# calculator2.net
KiCad netlist of a schematic drawn in EAGLE
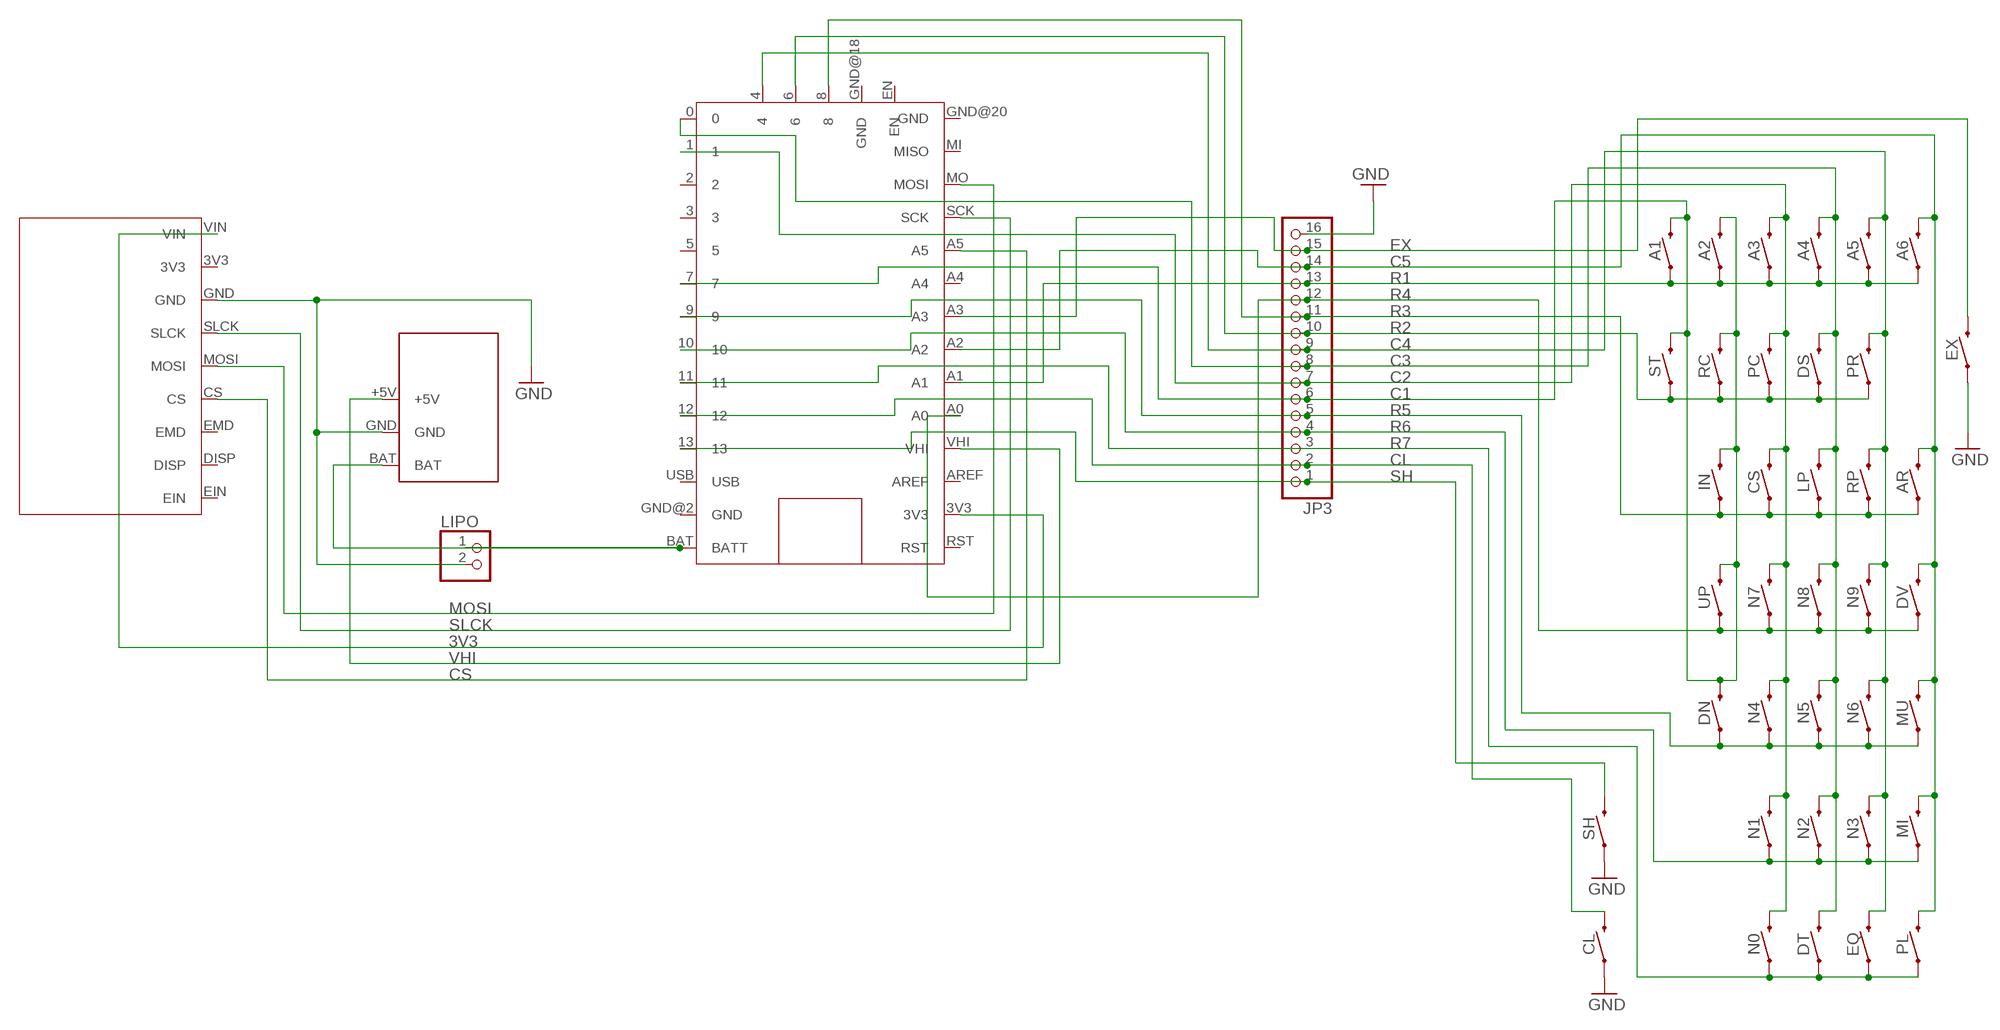
[diagram p0: schematic, sheet 1]

(export (version "E")
  (design (tool "Eeschema 10.0.6"))
  (components
    (comp (ref "A1")
      (value "MOMENTARY-SWITCH-SPST-PTH-6.0MM")
      (footprint "eagle-import:TACTILE_SWITCH_PTH_6.0MM")
      (libsource (lib "eagle-import") (part "MOMENTARY-SWITCH-SPST-PTH-6.0MM"))
    )
    (comp (ref "A2")
      (value "MOMENTARY-SWITCH-SPST-PTH-6.0MM")
      (footprint "eagle-import:TACTILE_SWITCH_PTH_6.0MM")
      (libsource (lib "eagle-import") (part "MOMENTARY-SWITCH-SPST-PTH-6.0MM"))
    )
    (comp (ref "A3")
      (value "MOMENTARY-SWITCH-SPST-PTH-6.0MM")
      (footprint "eagle-import:TACTILE_SWITCH_PTH_6.0MM")
      (libsource (lib "eagle-import") (part "MOMENTARY-SWITCH-SPST-PTH-6.0MM"))
    )
    (comp (ref "A4")
      (value "MOMENTARY-SWITCH-SPST-PTH-6.0MM")
      (footprint "eagle-import:TACTILE_SWITCH_PTH_6.0MM")
      (libsource (lib "eagle-import") (part "MOMENTARY-SWITCH-SPST-PTH-6.0MM"))
    )
    (comp (ref "A5")
      (value "MOMENTARY-SWITCH-SPST-PTH-6.0MM")
      (footprint "eagle-import:TACTILE_SWITCH_PTH_6.0MM")
      (libsource (lib "eagle-import") (part "MOMENTARY-SWITCH-SPST-PTH-6.0MM"))
    )
    (comp (ref "A6")
      (value "MOMENTARY-SWITCH-SPST-PTH-6.0MM")
      (footprint "eagle-import:TACTILE_SWITCH_PTH_6.0MM")
      (libsource (lib "eagle-import") (part "MOMENTARY-SWITCH-SPST-PTH-6.0MM"))
    )
    (comp (ref "AR")
      (value "MOMENTARY-SWITCH-SPST-PTH-6.0MM")
      (footprint "eagle-import:TACTILE_SWITCH_PTH_6.0MM")
      (libsource (lib "eagle-import") (part "MOMENTARY-SWITCH-SPST-PTH-6.0MM"))
    )
    (comp (ref "CHARGER")
      (value "PROTRINKET")
      (footprint "eagle-import:PROTRINKET")
      (libsource (lib "eagle-import") (part "PROTRINKET"))
    )
    (comp (ref "CL")
      (value "MOMENTARY-SWITCH-SPST-PTH-6.0MM")
      (footprint "eagle-import:TACTILE_SWITCH_PTH_6.0MM")
      (libsource (lib "eagle-import") (part "MOMENTARY-SWITCH-SPST-PTH-6.0MM"))
    )
    (comp (ref "CONTROLLER")
      (value "IB32U4")
      (footprint "eagle-import:IB32U4")
      (libsource (lib "eagle-import") (part "IB32U4"))
    )
    (comp (ref "CS")
      (value "MOMENTARY-SWITCH-SPST-PTH-6.0MM")
      (footprint "eagle-import:TACTILE_SWITCH_PTH_6.0MM")
      (libsource (lib "eagle-import") (part "MOMENTARY-SWITCH-SPST-PTH-6.0MM"))
    )
    (comp (ref "DN")
      (value "MOMENTARY-SWITCH-SPST-PTH-6.0MM")
      (footprint "eagle-import:TACTILE_SWITCH_PTH_6.0MM")
      (libsource (lib "eagle-import") (part "MOMENTARY-SWITCH-SPST-PTH-6.0MM"))
    )
    (comp (ref "DS")
      (value "MOMENTARY-SWITCH-SPST-PTH-6.0MM")
      (footprint "eagle-import:TACTILE_SWITCH_PTH_6.0MM")
      (libsource (lib "eagle-import") (part "MOMENTARY-SWITCH-SPST-PTH-6.0MM"))
    )
    (comp (ref "DT")
      (value "MOMENTARY-SWITCH-SPST-PTH-6.0MM")
      (footprint "eagle-import:TACTILE_SWITCH_PTH_6.0MM")
      (libsource (lib "eagle-import") (part "MOMENTARY-SWITCH-SPST-PTH-6.0MM"))
    )
    (comp (ref "DV")
      (value "MOMENTARY-SWITCH-SPST-PTH-6.0MM")
      (footprint "eagle-import:TACTILE_SWITCH_PTH_6.0MM")
      (libsource (lib "eagle-import") (part "MOMENTARY-SWITCH-SPST-PTH-6.0MM"))
    )
    (comp (ref "EQ")
      (value "MOMENTARY-SWITCH-SPST-PTH-6.0MM")
      (footprint "eagle-import:TACTILE_SWITCH_PTH_6.0MM")
      (libsource (lib "eagle-import") (part "MOMENTARY-SWITCH-SPST-PTH-6.0MM"))
    )
    (comp (ref "EX")
      (value "MOMENTARY-SWITCH-SPST-PTH-6.0MM")
      (footprint "eagle-import:TACTILE_SWITCH_PTH_6.0MM")
      (libsource (lib "eagle-import") (part "MOMENTARY-SWITCH-SPST-PTH-6.0MM"))
    )
    (comp (ref "IN")
      (value "MOMENTARY-SWITCH-SPST-PTH-6.0MM")
      (footprint "eagle-import:TACTILE_SWITCH_PTH_6.0MM")
      (libsource (lib "eagle-import") (part "MOMENTARY-SWITCH-SPST-PTH-6.0MM"))
    )
    (comp (ref "JP3")
      (value "PINHD-1X16")
      (footprint "eagle-import:1X16")
      (libsource (lib "eagle-import") (part "PINHD-1X16"))
    )
    (comp (ref "LIPO")
      (value "PINHD-1X2")
      (footprint "eagle-import:1X02")
      (libsource (lib "eagle-import") (part "PINHD-1X2"))
    )
    (comp (ref "LP")
      (value "MOMENTARY-SWITCH-SPST-PTH-6.0MM")
      (footprint "eagle-import:TACTILE_SWITCH_PTH_6.0MM")
      (libsource (lib "eagle-import") (part "MOMENTARY-SWITCH-SPST-PTH-6.0MM"))
    )
    (comp (ref "MI")
      (value "MOMENTARY-SWITCH-SPST-PTH-6.0MM")
      (footprint "eagle-import:TACTILE_SWITCH_PTH_6.0MM")
      (libsource (lib "eagle-import") (part "MOMENTARY-SWITCH-SPST-PTH-6.0MM"))
    )
    (comp (ref "MU")
      (value "MOMENTARY-SWITCH-SPST-PTH-6.0MM")
      (footprint "eagle-import:TACTILE_SWITCH_PTH_6.0MM")
      (libsource (lib "eagle-import") (part "MOMENTARY-SWITCH-SPST-PTH-6.0MM"))
    )
    (comp (ref "N0")
      (value "MOMENTARY-SWITCH-SPST-PTH-6.0MM")
      (footprint "eagle-import:TACTILE_SWITCH_PTH_6.0MM")
      (libsource (lib "eagle-import") (part "MOMENTARY-SWITCH-SPST-PTH-6.0MM"))
    )
    (comp (ref "N1")
      (value "MOMENTARY-SWITCH-SPST-PTH-6.0MM")
      (footprint "eagle-import:TACTILE_SWITCH_PTH_6.0MM")
      (libsource (lib "eagle-import") (part "MOMENTARY-SWITCH-SPST-PTH-6.0MM"))
    )
    (comp (ref "N2")
      (value "MOMENTARY-SWITCH-SPST-PTH-6.0MM")
      (footprint "eagle-import:TACTILE_SWITCH_PTH_6.0MM")
      (libsource (lib "eagle-import") (part "MOMENTARY-SWITCH-SPST-PTH-6.0MM"))
    )
    (comp (ref "N3")
      (value "MOMENTARY-SWITCH-SPST-PTH-6.0MM")
      (footprint "eagle-import:TACTILE_SWITCH_PTH_6.0MM")
      (libsource (lib "eagle-import") (part "MOMENTARY-SWITCH-SPST-PTH-6.0MM"))
    )
    (comp (ref "N4")
      (value "MOMENTARY-SWITCH-SPST-PTH-6.0MM")
      (footprint "eagle-import:TACTILE_SWITCH_PTH_6.0MM")
      (libsource (lib "eagle-import") (part "MOMENTARY-SWITCH-SPST-PTH-6.0MM"))
    )
    (comp (ref "N5")
      (value "MOMENTARY-SWITCH-SPST-PTH-6.0MM")
      (footprint "eagle-import:TACTILE_SWITCH_PTH_6.0MM")
      (libsource (lib "eagle-import") (part "MOMENTARY-SWITCH-SPST-PTH-6.0MM"))
    )
    (comp (ref "N6")
      (value "MOMENTARY-SWITCH-SPST-PTH-6.0MM")
      (footprint "eagle-import:TACTILE_SWITCH_PTH_6.0MM")
      (libsource (lib "eagle-import") (part "MOMENTARY-SWITCH-SPST-PTH-6.0MM"))
    )
    (comp (ref "N7")
      (value "MOMENTARY-SWITCH-SPST-PTH-6.0MM")
      (footprint "eagle-import:TACTILE_SWITCH_PTH_6.0MM")
      (libsource (lib "eagle-import") (part "MOMENTARY-SWITCH-SPST-PTH-6.0MM"))
    )
    (comp (ref "N8")
      (value "MOMENTARY-SWITCH-SPST-PTH-6.0MM")
      (footprint "eagle-import:TACTILE_SWITCH_PTH_6.0MM")
      (libsource (lib "eagle-import") (part "MOMENTARY-SWITCH-SPST-PTH-6.0MM"))
    )
    (comp (ref "N9")
      (value "MOMENTARY-SWITCH-SPST-PTH-6.0MM")
      (footprint "eagle-import:TACTILE_SWITCH_PTH_6.0MM")
      (libsource (lib "eagle-import") (part "MOMENTARY-SWITCH-SPST-PTH-6.0MM"))
    )
    (comp (ref "PC")
      (value "MOMENTARY-SWITCH-SPST-PTH-6.0MM")
      (footprint "eagle-import:TACTILE_SWITCH_PTH_6.0MM")
      (libsource (lib "eagle-import") (part "MOMENTARY-SWITCH-SPST-PTH-6.0MM"))
    )
    (comp (ref "PL")
      (value "MOMENTARY-SWITCH-SPST-PTH-6.0MM")
      (footprint "eagle-import:TACTILE_SWITCH_PTH_6.0MM")
      (libsource (lib "eagle-import") (part "MOMENTARY-SWITCH-SPST-PTH-6.0MM"))
    )
    (comp (ref "PR")
      (value "MOMENTARY-SWITCH-SPST-PTH-6.0MM")
      (footprint "eagle-import:TACTILE_SWITCH_PTH_6.0MM")
      (libsource (lib "eagle-import") (part "MOMENTARY-SWITCH-SPST-PTH-6.0MM"))
    )
    (comp (ref "RC")
      (value "MOMENTARY-SWITCH-SPST-PTH-6.0MM")
      (footprint "eagle-import:TACTILE_SWITCH_PTH_6.0MM")
      (libsource (lib "eagle-import") (part "MOMENTARY-SWITCH-SPST-PTH-6.0MM"))
    )
    (comp (ref "RP")
      (value "MOMENTARY-SWITCH-SPST-PTH-6.0MM")
      (footprint "eagle-import:TACTILE_SWITCH_PTH_6.0MM")
      (libsource (lib "eagle-import") (part "MOMENTARY-SWITCH-SPST-PTH-6.0MM"))
    )
    (comp (ref "SH")
      (value "MOMENTARY-SWITCH-SPST-PTH-6.0MM")
      (footprint "eagle-import:TACTILE_SWITCH_PTH_6.0MM")
      (libsource (lib "eagle-import") (part "MOMENTARY-SWITCH-SPST-PTH-6.0MM"))
    )
    (comp (ref "SHARPMEM")
      (value "SHARPMEM")
      (footprint "eagle-import:SHARPMEM")
      (libsource (lib "eagle-import") (part "SHARPMEM"))
    )
    (comp (ref "ST")
      (value "MOMENTARY-SWITCH-SPST-PTH-6.0MM")
      (footprint "eagle-import:TACTILE_SWITCH_PTH_6.0MM")
      (libsource (lib "eagle-import") (part "MOMENTARY-SWITCH-SPST-PTH-6.0MM"))
    )
    (comp (ref "UP")
      (value "MOMENTARY-SWITCH-SPST-PTH-6.0MM")
      (footprint "eagle-import:TACTILE_SWITCH_PTH_6.0MM")
      (libsource (lib "eagle-import") (part "MOMENTARY-SWITCH-SPST-PTH-6.0MM"))
    )
  )
  (nets
    (net (code "1") (name "/3V3") (class "Default")
      (node (ref "CONTROLLER") (pin "3V3") (pinfunction "3V3_3V3") (pintype "bidirectional"))
      (node (ref "SHARPMEM") (pin "VIN") (pinfunction "VIN_VIN") (pintype "bidirectional"))
    )
    (net (code "2") (name "/C1") (class "Default")
      (node (ref "A1") (pin "3") (pinfunction "2_3") (pintype "passive"))
      (node (ref "A2") (pin "3") (pinfunction "2_3") (pintype "passive"))
      (node (ref "CONTROLLER") (pin "7") (pinfunction "7_7") (pintype "bidirectional"))
      (node (ref "DN") (pin "3") (pinfunction "2_3") (pintype "passive"))
      (node (ref "IN") (pin "3") (pinfunction "2_3") (pintype "passive"))
      (node (ref "JP3") (pin "6") (pinfunction "6_6") (pintype "passive"))
      (node (ref "RC") (pin "3") (pinfunction "2_3") (pintype "passive"))
      (node (ref "ST") (pin "3") (pinfunction "2_3") (pintype "passive"))
      (node (ref "UP") (pin "3") (pinfunction "2_3") (pintype "passive"))
    )
    (net (code "3") (name "/C2") (class "Default")
      (node (ref "A3") (pin "3") (pinfunction "2_3") (pintype "passive"))
      (node (ref "CONTROLLER") (pin "1") (pinfunction "1_1") (pintype "bidirectional"))
      (node (ref "CS") (pin "3") (pinfunction "2_3") (pintype "passive"))
      (node (ref "JP3") (pin "7") (pinfunction "7_7") (pintype "passive"))
      (node (ref "N0") (pin "3") (pinfunction "2_3") (pintype "passive"))
      (node (ref "N1") (pin "3") (pinfunction "2_3") (pintype "passive"))
      (node (ref "N4") (pin "3") (pinfunction "2_3") (pintype "passive"))
      (node (ref "N7") (pin "3") (pinfunction "2_3") (pintype "passive"))
      (node (ref "PC") (pin "3") (pinfunction "2_3") (pintype "passive"))
    )
    (net (code "4") (name "/C3") (class "Default")
      (node (ref "A4") (pin "3") (pinfunction "2_3") (pintype "passive"))
      (node (ref "CONTROLLER") (pin "0") (pinfunction "0_0") (pintype "bidirectional"))
      (node (ref "DS") (pin "3") (pinfunction "2_3") (pintype "passive"))
      (node (ref "DT") (pin "3") (pinfunction "2_3") (pintype "passive"))
      (node (ref "JP3") (pin "8") (pinfunction "8_8") (pintype "passive"))
      (node (ref "LP") (pin "3") (pinfunction "2_3") (pintype "passive"))
      (node (ref "N2") (pin "3") (pinfunction "2_3") (pintype "passive"))
      (node (ref "N5") (pin "3") (pinfunction "2_3") (pintype "passive"))
      (node (ref "N8") (pin "3") (pinfunction "2_3") (pintype "passive"))
    )
    (net (code "5") (name "/C4") (class "Default")
      (node (ref "A5") (pin "3") (pinfunction "2_3") (pintype "passive"))
      (node (ref "CONTROLLER") (pin "4") (pinfunction "4_4") (pintype "bidirectional"))
      (node (ref "EQ") (pin "3") (pinfunction "2_3") (pintype "passive"))
      (node (ref "JP3") (pin "9") (pinfunction "9_9") (pintype "passive"))
      (node (ref "N3") (pin "3") (pinfunction "2_3") (pintype "passive"))
      (node (ref "N6") (pin "3") (pinfunction "2_3") (pintype "passive"))
      (node (ref "N9") (pin "3") (pinfunction "2_3") (pintype "passive"))
      (node (ref "PR") (pin "3") (pinfunction "2_3") (pintype "passive"))
      (node (ref "RP") (pin "3") (pinfunction "2_3") (pintype "passive"))
    )
    (net (code "6") (name "/C5") (class "Default")
      (node (ref "A6") (pin "3") (pinfunction "2_3") (pintype "passive"))
      (node (ref "AR") (pin "3") (pinfunction "2_3") (pintype "passive"))
      (node (ref "CONTROLLER") (pin "A2") (pinfunction "A2_A2") (pintype "bidirectional"))
      (node (ref "DV") (pin "3") (pinfunction "2_3") (pintype "passive"))
      (node (ref "JP3") (pin "14") (pinfunction "14_14") (pintype "passive"))
      (node (ref "MI") (pin "3") (pinfunction "2_3") (pintype "passive"))
      (node (ref "MU") (pin "3") (pinfunction "2_3") (pintype "passive"))
      (node (ref "PL") (pin "3") (pinfunction "2_3") (pintype "passive"))
    )
    (net (code "7") (name "/CL") (class "Default")
      (node (ref "CL") (pin "3") (pinfunction "2_3") (pintype "passive"))
      (node (ref "CONTROLLER") (pin "12") (pinfunction "12_12") (pintype "bidirectional"))
      (node (ref "JP3") (pin "2") (pinfunction "2_2") (pintype "passive"))
    )
    (net (code "8") (name "/CS") (class "Default")
      (node (ref "CONTROLLER") (pin "A5") (pinfunction "A5_A5") (pintype "bidirectional"))
      (node (ref "SHARPMEM") (pin "CS") (pinfunction "CS_CS") (pintype "bidirectional"))
    )
    (net (code "9") (name "/EX") (class "Default")
      (node (ref "CONTROLLER") (pin "A3") (pinfunction "A3_A3") (pintype "bidirectional"))
      (node (ref "EX") (pin "3") (pinfunction "2_3") (pintype "passive"))
      (node (ref "JP3") (pin "15") (pinfunction "15_15") (pintype "passive"))
    )
    (net (code "10") (name "/MOSI") (class "Default")
      (node (ref "CONTROLLER") (pin "MO") (pinfunction "MOSI_MO") (pintype "bidirectional"))
      (node (ref "SHARPMEM") (pin "MOSI") (pinfunction "MOSI_MOSI") (pintype "bidirectional"))
    )
    (net (code "11") (name "/R1") (class "Default")
      (node (ref "A1") (pin "1") (pinfunction "1_1") (pintype "passive"))
      (node (ref "A2") (pin "1") (pinfunction "1_1") (pintype "passive"))
      (node (ref "A3") (pin "1") (pinfunction "1_1") (pintype "passive"))
      (node (ref "A4") (pin "1") (pinfunction "1_1") (pintype "passive"))
      (node (ref "A5") (pin "1") (pinfunction "1_1") (pintype "passive"))
      (node (ref "A6") (pin "1") (pinfunction "1_1") (pintype "passive"))
      (node (ref "CONTROLLER") (pin "A1") (pinfunction "A1_A1") (pintype "bidirectional"))
      (node (ref "JP3") (pin "13") (pinfunction "13_13") (pintype "passive"))
    )
    (net (code "12") (name "/R2") (class "Default")
      (node (ref "CONTROLLER") (pin "6") (pinfunction "6_6") (pintype "bidirectional"))
      (node (ref "DS") (pin "1") (pinfunction "1_1") (pintype "passive"))
      (node (ref "JP3") (pin "10") (pinfunction "10_10") (pintype "passive"))
      (node (ref "PC") (pin "1") (pinfunction "1_1") (pintype "passive"))
      (node (ref "PR") (pin "1") (pinfunction "1_1") (pintype "passive"))
      (node (ref "RC") (pin "1") (pinfunction "1_1") (pintype "passive"))
      (node (ref "ST") (pin "1") (pinfunction "1_1") (pintype "passive"))
    )
    (net (code "13") (name "/R3") (class "Default")
      (node (ref "AR") (pin "1") (pinfunction "1_1") (pintype "passive"))
      (node (ref "CONTROLLER") (pin "8") (pinfunction "8_8") (pintype "bidirectional"))
      (node (ref "CS") (pin "1") (pinfunction "1_1") (pintype "passive"))
      (node (ref "IN") (pin "1") (pinfunction "1_1") (pintype "passive"))
      (node (ref "JP3") (pin "11") (pinfunction "11_11") (pintype "passive"))
      (node (ref "LP") (pin "1") (pinfunction "1_1") (pintype "passive"))
      (node (ref "RP") (pin "1") (pinfunction "1_1") (pintype "passive"))
    )
    (net (code "14") (name "/R4") (class "Default")
      (node (ref "CONTROLLER") (pin "A0") (pinfunction "A0_A0") (pintype "bidirectional"))
      (node (ref "DV") (pin "1") (pinfunction "1_1") (pintype "passive"))
      (node (ref "JP3") (pin "12") (pinfunction "12_12") (pintype "passive"))
      (node (ref "N7") (pin "1") (pinfunction "1_1") (pintype "passive"))
      (node (ref "N8") (pin "1") (pinfunction "1_1") (pintype "passive"))
      (node (ref "N9") (pin "1") (pinfunction "1_1") (pintype "passive"))
      (node (ref "UP") (pin "1") (pinfunction "1_1") (pintype "passive"))
    )
    (net (code "15") (name "/R5") (class "Default")
      (node (ref "CONTROLLER") (pin "9") (pinfunction "9_9") (pintype "bidirectional"))
      (node (ref "DN") (pin "1") (pinfunction "1_1") (pintype "passive"))
      (node (ref "JP3") (pin "5") (pinfunction "5_5") (pintype "passive"))
      (node (ref "MU") (pin "1") (pinfunction "1_1") (pintype "passive"))
      (node (ref "N4") (pin "1") (pinfunction "1_1") (pintype "passive"))
      (node (ref "N5") (pin "1") (pinfunction "1_1") (pintype "passive"))
      (node (ref "N6") (pin "1") (pinfunction "1_1") (pintype "passive"))
    )
    (net (code "16") (name "/R6") (class "Default")
      (node (ref "CONTROLLER") (pin "10") (pinfunction "10_10") (pintype "bidirectional"))
      (node (ref "JP3") (pin "4") (pinfunction "4_4") (pintype "passive"))
      (node (ref "MI") (pin "1") (pinfunction "1_1") (pintype "passive"))
      (node (ref "N1") (pin "1") (pinfunction "1_1") (pintype "passive"))
      (node (ref "N2") (pin "1") (pinfunction "1_1") (pintype "passive"))
      (node (ref "N3") (pin "1") (pinfunction "1_1") (pintype "passive"))
    )
    (net (code "17") (name "/R7") (class "Default")
      (node (ref "CONTROLLER") (pin "11") (pinfunction "11_11") (pintype "bidirectional"))
      (node (ref "DT") (pin "1") (pinfunction "1_1") (pintype "passive"))
      (node (ref "EQ") (pin "1") (pinfunction "1_1") (pintype "passive"))
      (node (ref "JP3") (pin "3") (pinfunction "3_3") (pintype "passive"))
      (node (ref "N0") (pin "1") (pinfunction "1_1") (pintype "passive"))
      (node (ref "PL") (pin "1") (pinfunction "1_1") (pintype "passive"))
    )
    (net (code "18") (name "/SH") (class "Default")
      (node (ref "CONTROLLER") (pin "13") (pinfunction "13_13") (pintype "bidirectional"))
      (node (ref "JP3") (pin "1") (pinfunction "1_1") (pintype "passive"))
      (node (ref "SH") (pin "3") (pinfunction "2_3") (pintype "passive"))
    )
    (net (code "19") (name "/SLCK") (class "Default")
      (node (ref "CONTROLLER") (pin "SCK") (pinfunction "SCK_SCK") (pintype "bidirectional"))
      (node (ref "SHARPMEM") (pin "SLCK") (pinfunction "SLCK_SLCK") (pintype "bidirectional"))
    )
    (net (code "20") (name "/VHI") (class "Default")
      (node (ref "CHARGER") (pin "+5V") (pinfunction "+5V_+5V") (pintype "bidirectional"))
      (node (ref "CONTROLLER") (pin "VHI") (pinfunction "VHI_VHI") (pintype "bidirectional"))
    )
    (net (code "21") (name "GND") (class "Default")
      (node (ref "CHARGER") (pin "GND") (pinfunction "GND_GND") (pintype "bidirectional"))
      (node (ref "CL") (pin "1") (pinfunction "1_1") (pintype "passive"))
      (node (ref "EX") (pin "1") (pinfunction "1_1") (pintype "passive"))
      (node (ref "JP3") (pin "16") (pinfunction "16_16") (pintype "passive"))
      (node (ref "LIPO") (pin "2") (pinfunction "2_2") (pintype "passive"))
      (node (ref "SH") (pin "1") (pinfunction "1_1") (pintype "passive"))
      (node (ref "SHARPMEM") (pin "GND") (pinfunction "GND_GND") (pintype "bidirectional"))
    )
    (net (code "22") (name "Net-(CONTROLLER-BATT)") (class "Default")
      (node (ref "CHARGER") (pin "BAT") (pinfunction "BAT_BAT") (pintype "bidirectional"))
      (node (ref "CONTROLLER") (pin "BAT") (pinfunction "BATT_BAT") (pintype "bidirectional"))
      (node (ref "LIPO") (pin "1") (pinfunction "1_1") (pintype "passive"))
    )
    (net (code "23") (name "unconnected-(CONTROLLER-GND-PadGND@2)") (class "Default")
      (node (ref "CONTROLLER") (pin "GND@2") (pinfunction "GND_GND@2") (pintype "bidirectional"))
    )
    (net (code "24") (name "unconnected-(CONTROLLER-GND-PadGND@18)") (class "Default")
      (node (ref "CONTROLLER") (pin "GND@18") (pinfunction "GND_GND@18") (pintype "bidirectional"))
    )
    (net (code "25") (name "unconnected-(CONTROLLER-GND-PadGND@20)") (class "Default")
      (node (ref "CONTROLLER") (pin "GND@20") (pinfunction "GND_GND@20") (pintype "bidirectional"))
    )
    (net (code "26") (name "unconnected-(CONTROLLER-MISO-PadMI)") (class "Default")
      (node (ref "CONTROLLER") (pin "MI") (pinfunction "MISO_MI") (pintype "bidirectional"))
    )
    (net (code "27") (name "unconnected-(CONTROLLER-Pad2)") (class "Default")
      (node (ref "CONTROLLER") (pin "2") (pinfunction "2_2") (pintype "bidirectional"))
    )
    (net (code "28") (name "unconnected-(CONTROLLER-Pad3)") (class "Default")
      (node (ref "CONTROLLER") (pin "3") (pinfunction "3_3") (pintype "bidirectional"))
    )
    (net (code "29") (name "unconnected-(CONTROLLER-Pad5)") (class "Default")
      (node (ref "CONTROLLER") (pin "5") (pinfunction "5_5") (pintype "bidirectional"))
    )
    (net (code "30") (name "unconnected-(CONTROLLER-PadA4)") (class "Default")
      (node (ref "CONTROLLER") (pin "A4") (pinfunction "A4_A4") (pintype "bidirectional"))
    )
    (net (code "31") (name "unconnected-(CONTROLLER-PadAREF)") (class "Default")
      (node (ref "CONTROLLER") (pin "AREF") (pinfunction "AREF_AREF") (pintype "bidirectional"))
    )
    (net (code "32") (name "unconnected-(CONTROLLER-PadEN)") (class "Default")
      (node (ref "CONTROLLER") (pin "EN") (pinfunction "EN_EN") (pintype "bidirectional"))
    )
    (net (code "33") (name "unconnected-(CONTROLLER-PadRST)") (class "Default")
      (node (ref "CONTROLLER") (pin "RST") (pinfunction "RST_RST") (pintype "bidirectional"))
    )
    (net (code "34") (name "unconnected-(CONTROLLER-PadUSB)") (class "Default")
      (node (ref "CONTROLLER") (pin "USB") (pinfunction "USB_USB") (pintype "bidirectional"))
    )
    (net (code "35") (name "unconnected-(SHARPMEM-Pad3V3)") (class "Default")
      (node (ref "SHARPMEM") (pin "3V3") (pinfunction "3V3_3V3") (pintype "bidirectional"))
    )
    (net (code "36") (name "unconnected-(SHARPMEM-PadDISP)") (class "Default")
      (node (ref "SHARPMEM") (pin "DISP") (pinfunction "DISP_DISP") (pintype "bidirectional"))
    )
    (net (code "37") (name "unconnected-(SHARPMEM-PadEIN)") (class "Default")
      (node (ref "SHARPMEM") (pin "EIN") (pinfunction "EIN_EIN") (pintype "bidirectional"))
    )
    (net (code "38") (name "unconnected-(SHARPMEM-PadEMD)") (class "Default")
      (node (ref "SHARPMEM") (pin "EMD") (pinfunction "EMD_EMD") (pintype "bidirectional"))
    )
  )
)
